# LCD.net
KiCad netlist of a schematic drawn in Altium Designer
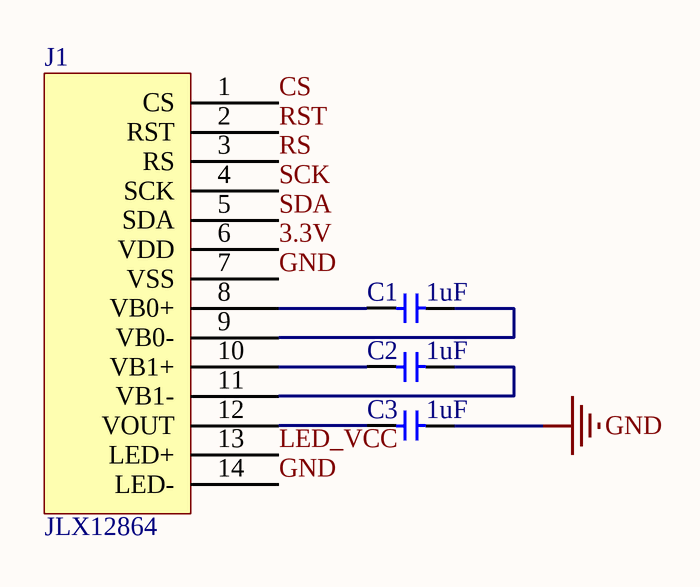
[diagram p0: LCD.SchDoc]

(export (version "E")
  (design (tool "Eeschema 10.0.6"))
  (components
    (comp (ref "C1")
      (value "1uF")
      (footprint "0603-2")
      (description "无极性电容")
      (fields (field (name "Comment") "Cap") (field (name "PUBLISHER") "Altium Limited"))
      (libsource (lib "fszhang") (part "Cap"))
    )
    (comp (ref "C2")
      (value "1uF")
      (footprint "0603-2")
      (description "无极性电容")
      (fields (field (name "Comment") "Cap") (field (name "PUBLISHER") "Altium Limited"))
      (libsource (lib "fszhang") (part "Cap"))
    )
    (comp (ref "C3")
      (value "1uF")
      (footprint "0603-2")
      (description "无极性电容")
      (fields (field (name "Comment") "Cap") (field (name "PUBLISHER") "Altium Limited"))
      (libsource (lib "fszhang") (part "Cap"))
    )
    (comp (ref "J1")
      (value "JLX12864")
      (footprint "JLX12864")
      (description "12864点阵屏")
      (libsource (lib "fszhang") (part "JLX12864"))
    )
  )
  (nets
    (net (code "1") (name "/3.3V") (class "Default")
      (node (ref "J1") (pin "6") (pinfunction "VDD_6") (pintype "passive"))
    )
    (net (code "2") (name "/CS") (class "Default")
      (node (ref "J1") (pin "1") (pinfunction "CS_1") (pintype "passive"))
    )
    (net (code "3") (name "/LED_VCC") (class "Default")
      (node (ref "J1") (pin "13") (pinfunction "LED+_13") (pintype "passive"))
    )
    (net (code "4") (name "/RS") (class "Default")
      (node (ref "J1") (pin "3") (pinfunction "RS_3") (pintype "passive"))
    )
    (net (code "5") (name "/RST") (class "Default")
      (node (ref "J1") (pin "2") (pinfunction "RST_2") (pintype "passive"))
    )
    (net (code "6") (name "/SCK") (class "Default")
      (node (ref "J1") (pin "4") (pinfunction "SCK_4") (pintype "passive"))
    )
    (net (code "7") (name "/SDA") (class "Default")
      (node (ref "J1") (pin "5") (pinfunction "SDA_5") (pintype "passive"))
    )
    (net (code "8") (name "GND") (class "Default")
      (node (ref "C3") (pin "2") (pinfunction "2_2") (pintype "passive"))
      (node (ref "J1") (pin "14") (pinfunction "LED-_14") (pintype "passive"))
      (node (ref "J1") (pin "7") (pinfunction "VSS_7") (pintype "passive"))
    )
    (net (code "9") (name "Net-(J1-VB0+)") (class "Default")
      (node (ref "C1") (pin "1") (pinfunction "1_1") (pintype "passive"))
      (node (ref "J1") (pin "8") (pinfunction "VB0+_8") (pintype "passive"))
    )
    (net (code "10") (name "Net-(J1-VB0-)") (class "Default")
      (node (ref "C1") (pin "2") (pinfunction "2_2") (pintype "passive"))
      (node (ref "J1") (pin "9") (pinfunction "VB0-_9") (pintype "passive"))
    )
    (net (code "11") (name "Net-(J1-VB1+)") (class "Default")
      (node (ref "C2") (pin "1") (pinfunction "1_1") (pintype "passive"))
      (node (ref "J1") (pin "10") (pinfunction "VB1+_10") (pintype "passive"))
    )
    (net (code "12") (name "Net-(J1-VB1-)") (class "Default")
      (node (ref "C2") (pin "2") (pinfunction "2_2") (pintype "passive"))
      (node (ref "J1") (pin "11") (pinfunction "VB1-_11") (pintype "passive"))
    )
    (net (code "13") (name "Net-(J1-VOUT)") (class "Default")
      (node (ref "C3") (pin "1") (pinfunction "1_1") (pintype "passive"))
      (node (ref "J1") (pin "12") (pinfunction "VOUT_12") (pintype "passive"))
    )
  )
)
